# main_board__PT.net
KiCad netlist of a schematic drawn in EAGLE
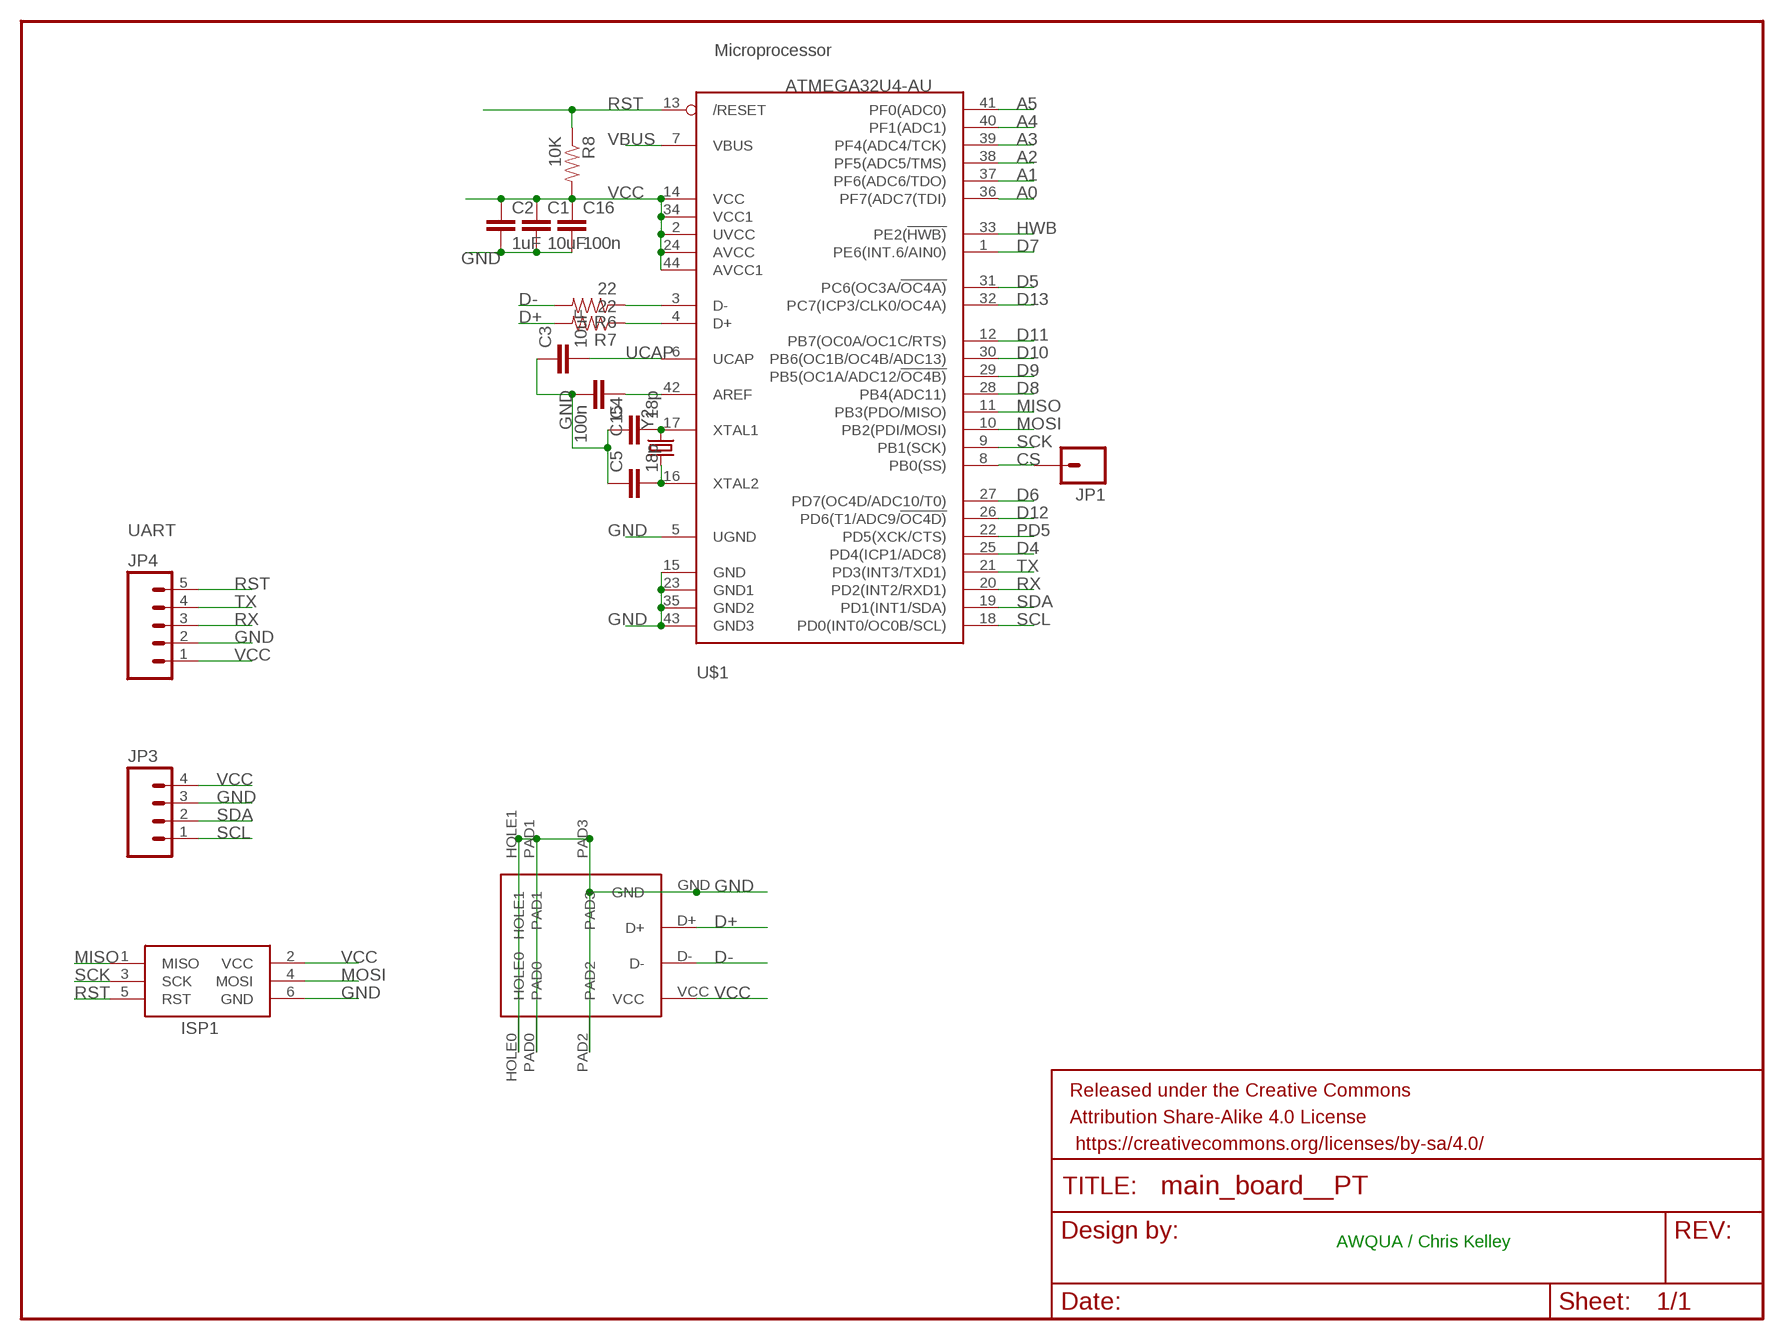
[diagram p0: schematic, sheet 1]

(export (version "E")
  (design (tool "Eeschema 10.0.6"))
  (components
    (comp (ref "C1")
      (value "10uF")
      (footprint "eagle-import:0603-CAP")
      (libsource (lib "eagle-import") (part "CAP0603-CAP"))
    )
    (comp (ref "C2")
      (value "1uF")
      (footprint "eagle-import:0603-CAP")
      (libsource (lib "eagle-import") (part "CAP0603-CAP"))
    )
    (comp (ref "C3")
      (value "10uF")
      (footprint "eagle-import:0603-CAP")
      (libsource (lib "eagle-import") (part "CAP0603-CAP"))
    )
    (comp (ref "C4")
      (value "18p")
      (footprint "eagle-import:0603-CAP")
      (libsource (lib "eagle-import") (part "CAP0603-CAP"))
    )
    (comp (ref "C5")
      (value "18p")
      (footprint "eagle-import:0603-CAP")
      (libsource (lib "eagle-import") (part "CAP0603-CAP"))
    )
    (comp (ref "C15")
      (value "100n")
      (footprint "eagle-import:0603-CAP")
      (libsource (lib "eagle-import") (part "CAP0603-CAP"))
    )
    (comp (ref "C16")
      (value "100n")
      (footprint "eagle-import:0603-CAP")
      (libsource (lib "eagle-import") (part "CAP0603-CAP"))
    )
    (comp (ref "FRAME2")
      (value "FRAME-LETTER")
      (footprint "eagle-import:CREATIVE_COMMONS")
      (libsource (lib "eagle-import") (part "FRAME-LETTER"))
    )
    (comp (ref "ISP1")
      (value "AVRISP-6")
      (footprint "eagle-import:AVRISP")
      (libsource (lib "eagle-import") (part "AVRISP-6"))
    )
    (comp (ref "JP1")
      (value "M01PTH")
      (footprint "eagle-import:1X01")
      (libsource (lib "eagle-import") (part "M01PTH"))
    )
    (comp (ref "JP3")
      (value "M04PTH")
      (footprint "eagle-import:1X04")
      (libsource (lib "eagle-import") (part "M04PTH"))
    )
    (comp (ref "JP4")
      (value "M05PTH")
      (footprint "eagle-import:1X05")
      (libsource (lib "eagle-import") (part "M05PTH"))
    )
    (comp (ref "R6")
      (value "22")
      (footprint "eagle-import:0603-RES")
      (libsource (lib "eagle-import") (part "RESISTOR0603"))
    )
    (comp (ref "R7")
      (value "22")
      (footprint "eagle-import:0603-RES")
      (libsource (lib "eagle-import") (part "RESISTOR0603"))
    )
    (comp (ref "R8")
      (value "10K")
      (footprint "eagle-import:1_6W-RES")
      (libsource (lib "eagle-import") (part "RESISTORPTH-1/6W"))
    )
    (comp (ref "U$1")
      (value "ATMEGA32U4-AU")
      (footprint "eagle-import:TQFP44")
      (libsource (lib "eagle-import") (part "ATMEGA32U4-AU"))
    )
    (comp (ref "U$2")
      (value "USBMICRO-10118193-0001LF")
      (footprint "eagle-import:USBMICRO-10118193-0001LF")
      (libsource (lib "eagle-import") (part "USBMICRO-10118193-0001LF"))
    )
    (comp (ref "Y2")
      (value "CRYSTAL5X3")
      (footprint "eagle-import:CRYSTAL-SMD-5X3")
      (libsource (lib "eagle-import") (part "CRYSTAL5X3"))
    )
  )
  (nets
    (net (code "1") (name "/A0") (class "Default")
      (node (ref "U$1") (pin "36") (pinfunction "PF7(ADC7(TDI)_36") (pintype "bidirectional"))
    )
    (net (code "2") (name "/A1") (class "Default")
      (node (ref "U$1") (pin "37") (pinfunction "PF6(ADC6/TDO)_37") (pintype "bidirectional"))
    )
    (net (code "3") (name "/A2") (class "Default")
      (node (ref "U$1") (pin "38") (pinfunction "PF5(ADC5/TMS)_38") (pintype "bidirectional"))
    )
    (net (code "4") (name "/A3") (class "Default")
      (node (ref "U$1") (pin "39") (pinfunction "PF4(ADC4/TCK)_39") (pintype "bidirectional"))
    )
    (net (code "5") (name "/A4") (class "Default")
      (node (ref "U$1") (pin "40") (pinfunction "PF1(ADC1)_40") (pintype "bidirectional"))
    )
    (net (code "6") (name "/A5") (class "Default")
      (node (ref "U$1") (pin "41") (pinfunction "PF0(ADC0)_41") (pintype "bidirectional"))
    )
    (net (code "7") (name "/CS") (class "Default")
      (node (ref "JP1") (pin "1") (pinfunction "1_1") (pintype "passive"))
      (node (ref "U$1") (pin "8") (pinfunction "PB0(SS)_8") (pintype "bidirectional"))
    )
    (net (code "8") (name "/D+") (class "Default")
      (node (ref "R7") (pin "2") (pinfunction "2_2") (pintype "passive"))
      (node (ref "U$2") (pin "D+") (pinfunction "D+_D+") (pintype "bidirectional"))
    )
    (net (code "9") (name "/D-") (class "Default")
      (node (ref "R6") (pin "2") (pinfunction "2_2") (pintype "passive"))
      (node (ref "U$2") (pin "D-") (pinfunction "D-_D-") (pintype "bidirectional"))
    )
    (net (code "10") (name "/D4") (class "Default")
      (node (ref "U$1") (pin "25") (pinfunction "PD4(ICP1/ADC8)_25") (pintype "bidirectional"))
    )
    (net (code "11") (name "/D5") (class "Default")
      (node (ref "U$1") (pin "31") (pinfunction "PC6(OC3A/~{OC4A})_31") (pintype "bidirectional"))
    )
    (net (code "12") (name "/D6") (class "Default")
      (node (ref "U$1") (pin "27") (pinfunction "PD7(OC4D/ADC10/T0)_27") (pintype "bidirectional"))
    )
    (net (code "13") (name "/D7") (class "Default")
      (node (ref "U$1") (pin "1") (pinfunction "PE6(INT.6/AIN0)_1") (pintype "bidirectional"))
    )
    (net (code "14") (name "/D8") (class "Default")
      (node (ref "U$1") (pin "28") (pinfunction "PB4(ADC11)_28") (pintype "bidirectional"))
    )
    (net (code "15") (name "/D9") (class "Default")
      (node (ref "U$1") (pin "29") (pinfunction "PB5(OC1A/ADC12/~{OC4B})_29") (pintype "bidirectional"))
    )
    (net (code "16") (name "/D10") (class "Default")
      (node (ref "U$1") (pin "30") (pinfunction "PB6(OC1B/OC4B/ADC13)_30") (pintype "bidirectional"))
    )
    (net (code "17") (name "/D11") (class "Default")
      (node (ref "U$1") (pin "12") (pinfunction "PB7(OC0A/OC1C/RTS)_12") (pintype "bidirectional"))
    )
    (net (code "18") (name "/D12") (class "Default")
      (node (ref "U$1") (pin "26") (pinfunction "PD6(T1/ADC9/~{OC4D})_26") (pintype "bidirectional"))
    )
    (net (code "19") (name "/D13") (class "Default")
      (node (ref "U$1") (pin "32") (pinfunction "PC7(ICP3/CLK0/OC4A)_32") (pintype "bidirectional"))
    )
    (net (code "20") (name "/GND") (class "Default")
      (node (ref "C1") (pin "2") (pinfunction "2_2") (pintype "passive"))
      (node (ref "C15") (pin "2") (pinfunction "2_2") (pintype "passive"))
      (node (ref "C16") (pin "2") (pinfunction "2_2") (pintype "passive"))
      (node (ref "C2") (pin "2") (pinfunction "2_2") (pintype "passive"))
      (node (ref "C3") (pin "1") (pinfunction "1_1") (pintype "passive"))
      (node (ref "C4") (pin "1") (pinfunction "1_1") (pintype "passive"))
      (node (ref "C5") (pin "1") (pinfunction "1_1") (pintype "passive"))
      (node (ref "ISP1") (pin "6") (pinfunction "GND_6") (pintype "power_in"))
      (node (ref "JP3") (pin "3") (pinfunction "3_3") (pintype "passive"))
      (node (ref "JP4") (pin "2") (pinfunction "2_2") (pintype "passive"))
      (node (ref "U$1") (pin "15") (pinfunction "GND_15") (pintype "bidirectional"))
      (node (ref "U$1") (pin "23") (pinfunction "GND1_23") (pintype "bidirectional"))
      (node (ref "U$1") (pin "35") (pinfunction "GND2_35") (pintype "bidirectional"))
      (node (ref "U$1") (pin "43") (pinfunction "GND3_43") (pintype "bidirectional"))
      (node (ref "U$1") (pin "5") (pinfunction "UGND_5") (pintype "bidirectional"))
      (node (ref "U$2") (pin "GND") (pinfunction "GND_GND") (pintype "bidirectional"))
      (node (ref "U$2") (pin "HOLE0") (pinfunction "HOLE0_HOLE0") (pintype "bidirectional"))
      (node (ref "U$2") (pin "HOLE1") (pinfunction "HOLE1_HOLE1") (pintype "bidirectional"))
      (node (ref "U$2") (pin "PAD0") (pinfunction "PAD0_PAD0") (pintype "bidirectional"))
      (node (ref "U$2") (pin "PAD1") (pinfunction "PAD1_PAD1") (pintype "bidirectional"))
      (node (ref "U$2") (pin "PAD2") (pinfunction "PAD2_PAD2") (pintype "bidirectional"))
      (node (ref "U$2") (pin "PAD3") (pinfunction "PAD3_PAD3") (pintype "bidirectional"))
    )
    (net (code "21") (name "/HWB") (class "Default")
      (node (ref "U$1") (pin "33") (pinfunction "PE2(~{HWB})_33") (pintype "bidirectional"))
    )
    (net (code "22") (name "/MISO") (class "Default")
      (node (ref "ISP1") (pin "1") (pinfunction "MISO_1") (pintype "input"))
      (node (ref "U$1") (pin "11") (pinfunction "PB3(PDO/MISO)_11") (pintype "bidirectional"))
    )
    (net (code "23") (name "/MOSI") (class "Default")
      (node (ref "ISP1") (pin "4") (pinfunction "MOSI_4") (pintype "output"))
      (node (ref "U$1") (pin "10") (pinfunction "PB2(PDI/MOSI)_10") (pintype "bidirectional"))
    )
    (net (code "24") (name "/PD5") (class "Default")
      (node (ref "U$1") (pin "22") (pinfunction "PD5(XCK/CTS)_22") (pintype "bidirectional"))
    )
    (net (code "25") (name "/RST") (class "Default")
      (node (ref "ISP1") (pin "5") (pinfunction "RST_5") (pintype "output"))
      (node (ref "JP4") (pin "5") (pinfunction "5_5") (pintype "passive"))
      (node (ref "R8") (pin "1") (pinfunction "1_1") (pintype "passive"))
      (node (ref "U$1") (pin "13") (pinfunction "/RESET_13") (pintype "bidirectional"))
    )
    (net (code "26") (name "/RX") (class "Default")
      (node (ref "JP4") (pin "3") (pinfunction "3_3") (pintype "passive"))
      (node (ref "U$1") (pin "20") (pinfunction "PD2(INT2/RXD1)_20") (pintype "bidirectional"))
    )
    (net (code "27") (name "/SCK") (class "Default")
      (node (ref "ISP1") (pin "3") (pinfunction "SCK_3") (pintype "output"))
      (node (ref "U$1") (pin "9") (pinfunction "PB1(SCK)_9") (pintype "bidirectional"))
    )
    (net (code "28") (name "/SCL") (class "Default")
      (node (ref "JP3") (pin "1") (pinfunction "1_1") (pintype "passive"))
      (node (ref "U$1") (pin "18") (pinfunction "PD0(INT0/OC0B/SCL)_18") (pintype "bidirectional"))
    )
    (net (code "29") (name "/SDA") (class "Default")
      (node (ref "JP3") (pin "2") (pinfunction "2_2") (pintype "passive"))
      (node (ref "U$1") (pin "19") (pinfunction "PD1(INT1/SDA)_19") (pintype "bidirectional"))
    )
    (net (code "30") (name "/TX") (class "Default")
      (node (ref "JP4") (pin "4") (pinfunction "4_4") (pintype "passive"))
      (node (ref "U$1") (pin "21") (pinfunction "PD3(INT3/TXD1)_21") (pintype "bidirectional"))
    )
    (net (code "31") (name "/UCAP") (class "Default")
      (node (ref "C3") (pin "2") (pinfunction "2_2") (pintype "passive"))
      (node (ref "U$1") (pin "6") (pinfunction "UCAP_6") (pintype "bidirectional"))
    )
    (net (code "32") (name "/VBUS") (class "Default")
      (node (ref "U$1") (pin "7") (pinfunction "VBUS_7") (pintype "bidirectional"))
    )
    (net (code "33") (name "/VCC") (class "Default")
      (node (ref "C1") (pin "1") (pinfunction "1_1") (pintype "passive"))
      (node (ref "C16") (pin "1") (pinfunction "1_1") (pintype "passive"))
      (node (ref "C2") (pin "1") (pinfunction "1_1") (pintype "passive"))
      (node (ref "ISP1") (pin "2") (pinfunction "VCC_2") (pintype "power_in"))
      (node (ref "JP3") (pin "4") (pinfunction "4_4") (pintype "passive"))
      (node (ref "JP4") (pin "1") (pinfunction "1_1") (pintype "passive"))
      (node (ref "R8") (pin "2") (pinfunction "2_2") (pintype "passive"))
      (node (ref "U$1") (pin "14") (pinfunction "VCC_14") (pintype "bidirectional"))
      (node (ref "U$1") (pin "2") (pinfunction "UVCC_2") (pintype "bidirectional"))
      (node (ref "U$1") (pin "24") (pinfunction "AVCC_24") (pintype "bidirectional"))
      (node (ref "U$1") (pin "34") (pinfunction "VCC1_34") (pintype "bidirectional"))
      (node (ref "U$1") (pin "44") (pinfunction "AVCC1_44") (pintype "bidirectional"))
      (node (ref "U$2") (pin "VCC") (pinfunction "VCC_VCC") (pintype "bidirectional"))
    )
    (net (code "34") (name "Net-(U$1-AREF)") (class "Default")
      (node (ref "C15") (pin "1") (pinfunction "1_1") (pintype "passive"))
      (node (ref "U$1") (pin "42") (pinfunction "AREF_42") (pintype "bidirectional"))
    )
    (net (code "35") (name "Net-(U$1-D+)") (class "Default")
      (node (ref "R7") (pin "1") (pinfunction "1_1") (pintype "passive"))
      (node (ref "U$1") (pin "4") (pinfunction "D+_4") (pintype "bidirectional"))
    )
    (net (code "36") (name "Net-(U$1-D-)") (class "Default")
      (node (ref "R6") (pin "1") (pinfunction "1_1") (pintype "passive"))
      (node (ref "U$1") (pin "3") (pinfunction "D-_3") (pintype "bidirectional"))
    )
    (net (code "37") (name "Net-(U$1-XTAL1)") (class "Default")
      (node (ref "C4") (pin "2") (pinfunction "2_2") (pintype "passive"))
      (node (ref "U$1") (pin "17") (pinfunction "XTAL1_17") (pintype "bidirectional"))
      (node (ref "Y2") (pin "3") (pinfunction "2_3") (pintype "passive"))
    )
    (net (code "38") (name "Net-(U$1-XTAL2)") (class "Default")
      (node (ref "C5") (pin "2") (pinfunction "2_2") (pintype "passive"))
      (node (ref "U$1") (pin "16") (pinfunction "XTAL2_16") (pintype "bidirectional"))
      (node (ref "Y2") (pin "1") (pinfunction "1_1") (pintype "passive"))
    )
  )
)
